# 03_LEDs_0_4.net
KiCad netlist of a schematic drawn in Altium Designer
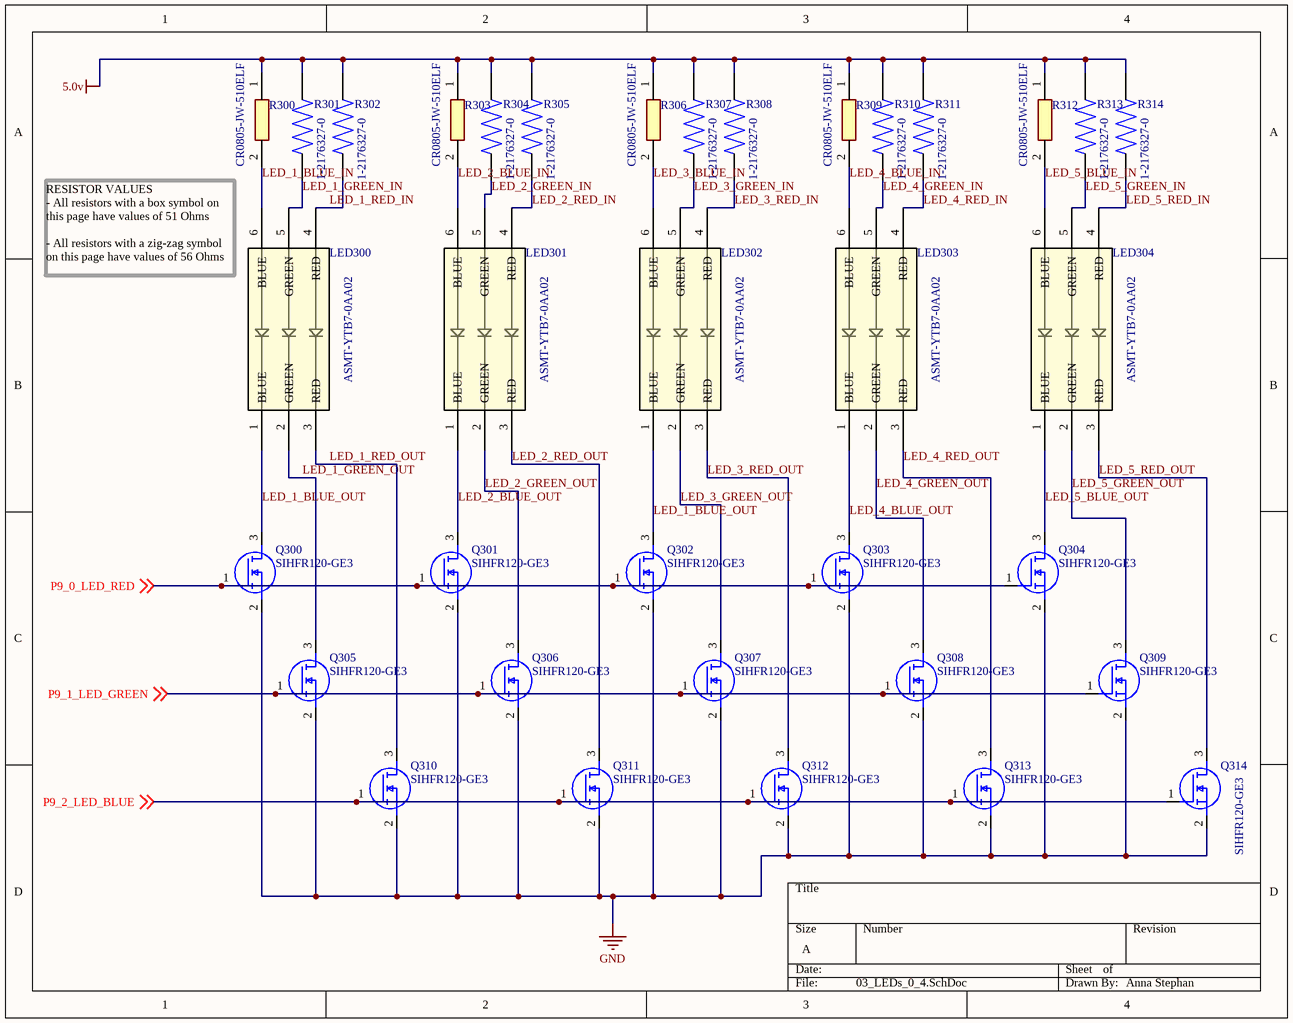
[diagram p0: 03_LEDs_0_4.SchDoc]

(export (version "E")
  (design (tool "Eeschema 10.0.6"))
  (components
    (comp (ref "LED300")
      (value "ASMT-YTB7-0AA02")
      (footprint "LED_ASMT-YTD7-0AA02")
      (description "No Description Available")
      (fields (field (name "COPYRIGHT") "Copyright (C) 2022 Ultra Librarian. All rights reserved."))
      (libsource (lib "453lib") (part "ASMT-YTB7-0AA02"))
    )
    (comp (ref "LED301")
      (value "ASMT-YTB7-0AA02")
      (footprint "LED_ASMT-YTD7-0AA02")
      (description "No Description Available")
      (fields (field (name "COPYRIGHT") "Copyright (C) 2022 Ultra Librarian. All rights reserved."))
      (libsource (lib "453lib") (part "ASMT-YTB7-0AA02"))
    )
    (comp (ref "LED302")
      (value "ASMT-YTB7-0AA02")
      (footprint "LED_ASMT-YTD7-0AA02")
      (description "No Description Available")
      (fields (field (name "COPYRIGHT") "Copyright (C) 2022 Ultra Librarian. All rights reserved."))
      (libsource (lib "453lib") (part "ASMT-YTB7-0AA02"))
    )
    (comp (ref "LED303")
      (value "ASMT-YTB7-0AA02")
      (footprint "LED_ASMT-YTD7-0AA02")
      (description "No Description Available")
      (fields (field (name "COPYRIGHT") "Copyright (C) 2022 Ultra Librarian. All rights reserved."))
      (libsource (lib "453lib") (part "ASMT-YTB7-0AA02"))
    )
    (comp (ref "LED304")
      (value "ASMT-YTB7-0AA02")
      (footprint "LED_ASMT-YTD7-0AA02")
      (description "No Description Available")
      (fields (field (name "COPYRIGHT") "Copyright (C) 2022 Ultra Librarian. All rights reserved."))
      (libsource (lib "453lib") (part "ASMT-YTB7-0AA02"))
    )
    (comp (ref "Q300")
      (value "SIHFR120-GE3")
      (footprint "SIHFR120GE3")
      (description "MOSFET (N-Channel)")
      (libsource (lib "453lib") (part "SIHFR120-GE3"))
    )
    (comp (ref "Q301")
      (value "SIHFR120-GE3")
      (footprint "SIHFR120GE3")
      (description "MOSFET (N-Channel)")
      (libsource (lib "453lib") (part "SIHFR120-GE3"))
    )
    (comp (ref "Q302")
      (value "SIHFR120-GE3")
      (footprint "SIHFR120GE3")
      (description "MOSFET (N-Channel)")
      (libsource (lib "453lib") (part "SIHFR120-GE3"))
    )
    (comp (ref "Q303")
      (value "SIHFR120-GE3")
      (footprint "SIHFR120GE3")
      (description "MOSFET (N-Channel)")
      (libsource (lib "453lib") (part "SIHFR120-GE3"))
    )
    (comp (ref "Q304")
      (value "SIHFR120-GE3")
      (footprint "SIHFR120GE3")
      (description "MOSFET (N-Channel)")
      (libsource (lib "453lib") (part "SIHFR120-GE3"))
    )
    (comp (ref "Q305")
      (value "SIHFR120-GE3")
      (footprint "SIHFR120GE3")
      (description "MOSFET (N-Channel)")
      (libsource (lib "453lib") (part "SIHFR120-GE3"))
    )
    (comp (ref "Q306")
      (value "SIHFR120-GE3")
      (footprint "SIHFR120GE3")
      (description "MOSFET (N-Channel)")
      (libsource (lib "453lib") (part "SIHFR120-GE3"))
    )
    (comp (ref "Q307")
      (value "SIHFR120-GE3")
      (footprint "SIHFR120GE3")
      (description "MOSFET (N-Channel)")
      (libsource (lib "453lib") (part "SIHFR120-GE3"))
    )
    (comp (ref "Q308")
      (value "SIHFR120-GE3")
      (footprint "SIHFR120GE3")
      (description "MOSFET (N-Channel)")
      (libsource (lib "453lib") (part "SIHFR120-GE3"))
    )
    (comp (ref "Q309")
      (value "SIHFR120-GE3")
      (footprint "SIHFR120GE3")
      (description "MOSFET (N-Channel)")
      (libsource (lib "453lib") (part "SIHFR120-GE3"))
    )
    (comp (ref "Q310")
      (value "SIHFR120-GE3")
      (footprint "SIHFR120GE3")
      (description "MOSFET (N-Channel)")
      (libsource (lib "453lib") (part "SIHFR120-GE3"))
    )
    (comp (ref "Q311")
      (value "SIHFR120-GE3")
      (footprint "SIHFR120GE3")
      (description "MOSFET (N-Channel)")
      (libsource (lib "453lib") (part "SIHFR120-GE3"))
    )
    (comp (ref "Q312")
      (value "SIHFR120-GE3")
      (footprint "SIHFR120GE3")
      (description "MOSFET (N-Channel)")
      (libsource (lib "453lib") (part "SIHFR120-GE3"))
    )
    (comp (ref "Q313")
      (value "SIHFR120-GE3")
      (footprint "SIHFR120GE3")
      (description "MOSFET (N-Channel)")
      (libsource (lib "453lib") (part "SIHFR120-GE3"))
    )
    (comp (ref "Q314")
      (value "SIHFR120-GE3")
      (footprint "SIHFR120GE3")
      (description "MOSFET (N-Channel)")
      (libsource (lib "453lib") (part "SIHFR120-GE3"))
    )
    (comp (ref "R300")
      (value "CR0805-JW-510ELF")
      (footprint "RESC2012X60N")
      (description "Resistor")
      (libsource (lib "453lib") (part "CR0805-JW-510ELF"))
    )
    (comp (ref "R301")
      (value "1-2176327-0")
      (footprint "RESC2012X65N")
      (description "Fixed Resistor CRGP 0805 56R 1%")
      (libsource (lib "453lib") (part "1-2176327-0"))
    )
    (comp (ref "R302")
      (value "1-2176327-0")
      (footprint "RESC2012X65N")
      (description "Fixed Resistor CRGP 0805 56R 1%")
      (libsource (lib "453lib") (part "1-2176327-0"))
    )
    (comp (ref "R303")
      (value "CR0805-JW-510ELF")
      (footprint "RESC2012X60N")
      (description "Resistor")
      (libsource (lib "453lib") (part "CR0805-JW-510ELF"))
    )
    (comp (ref "R304")
      (value "1-2176327-0")
      (footprint "RESC2012X65N")
      (description "Fixed Resistor CRGP 0805 56R 1%")
      (libsource (lib "453lib") (part "1-2176327-0"))
    )
    (comp (ref "R305")
      (value "1-2176327-0")
      (footprint "RESC2012X65N")
      (description "Fixed Resistor CRGP 0805 56R 1%")
      (libsource (lib "453lib") (part "1-2176327-0"))
    )
    (comp (ref "R306")
      (value "CR0805-JW-510ELF")
      (footprint "RESC2012X60N")
      (description "Resistor")
      (libsource (lib "453lib") (part "CR0805-JW-510ELF"))
    )
    (comp (ref "R307")
      (value "1-2176327-0")
      (footprint "RESC2012X65N")
      (description "Fixed Resistor CRGP 0805 56R 1%")
      (libsource (lib "453lib") (part "1-2176327-0"))
    )
    (comp (ref "R308")
      (value "1-2176327-0")
      (footprint "RESC2012X65N")
      (description "Fixed Resistor CRGP 0805 56R 1%")
      (libsource (lib "453lib") (part "1-2176327-0"))
    )
    (comp (ref "R309")
      (value "CR0805-JW-510ELF")
      (footprint "RESC2012X60N")
      (description "Resistor")
      (libsource (lib "453lib") (part "CR0805-JW-510ELF"))
    )
    (comp (ref "R310")
      (value "1-2176327-0")
      (footprint "RESC2012X65N")
      (description "Fixed Resistor CRGP 0805 56R 1%")
      (libsource (lib "453lib") (part "1-2176327-0"))
    )
    (comp (ref "R311")
      (value "1-2176327-0")
      (footprint "RESC2012X65N")
      (description "Fixed Resistor CRGP 0805 56R 1%")
      (libsource (lib "453lib") (part "1-2176327-0"))
    )
    (comp (ref "R312")
      (value "CR0805-JW-510ELF")
      (footprint "RESC2012X60N")
      (description "Resistor")
      (libsource (lib "453lib") (part "CR0805-JW-510ELF"))
    )
    (comp (ref "R313")
      (value "1-2176327-0")
      (footprint "RESC2012X65N")
      (description "Fixed Resistor CRGP 0805 56R 1%")
      (libsource (lib "453lib") (part "1-2176327-0"))
    )
    (comp (ref "R314")
      (value "1-2176327-0")
      (footprint "RESC2012X65N")
      (description "Fixed Resistor CRGP 0805 56R 1%")
      (libsource (lib "453lib") (part "1-2176327-0"))
    )
  )
  (nets
    (net (code "1") (name "/LED_1_BLUE_IN") (class "Default")
      (node (ref "LED300") (pin "6") (pinfunction "BLUE_6") (pintype "passive"))
      (node (ref "R300") (pin "2") (pinfunction "2_2") (pintype "passive"))
    )
    (net (code "2") (name "/LED_1_BLUE_OUT") (class "Default")
      (node (ref "LED300") (pin "1") (pinfunction "BLUE_1") (pintype "passive"))
      (node (ref "LED302") (pin "1") (pinfunction "BLUE_1") (pintype "passive"))
      (node (ref "Q300") (pin "3") (pinfunction "D_3") (pintype "passive"))
      (node (ref "Q302") (pin "3") (pinfunction "D_3") (pintype "passive"))
    )
    (net (code "3") (name "/LED_1_GREEN_IN") (class "Default")
      (node (ref "LED300") (pin "5") (pinfunction "GREEN_5") (pintype "passive"))
      (node (ref "R301") (pin "1") (pinfunction "1_1") (pintype "passive"))
    )
    (net (code "4") (name "/LED_1_GREEN_OUT") (class "Default")
      (node (ref "LED300") (pin "2") (pinfunction "GREEN_2") (pintype "passive"))
      (node (ref "Q305") (pin "3") (pinfunction "D_3") (pintype "passive"))
    )
    (net (code "5") (name "/LED_1_RED_IN") (class "Default")
      (node (ref "LED300") (pin "4") (pinfunction "RED_4") (pintype "passive"))
      (node (ref "R302") (pin "1") (pinfunction "1_1") (pintype "passive"))
    )
    (net (code "6") (name "/LED_1_RED_OUT") (class "Default")
      (node (ref "LED300") (pin "3") (pinfunction "RED_3") (pintype "passive"))
      (node (ref "Q310") (pin "3") (pinfunction "D_3") (pintype "passive"))
    )
    (net (code "7") (name "/LED_2_BLUE_IN") (class "Default")
      (node (ref "LED301") (pin "6") (pinfunction "BLUE_6") (pintype "passive"))
      (node (ref "R303") (pin "2") (pinfunction "2_2") (pintype "passive"))
    )
    (net (code "8") (name "/LED_2_BLUE_OUT") (class "Default")
      (node (ref "LED301") (pin "1") (pinfunction "BLUE_1") (pintype "passive"))
      (node (ref "Q301") (pin "3") (pinfunction "D_3") (pintype "passive"))
    )
    (net (code "9") (name "/LED_2_GREEN_IN") (class "Default")
      (node (ref "LED301") (pin "5") (pinfunction "GREEN_5") (pintype "passive"))
      (node (ref "R304") (pin "1") (pinfunction "1_1") (pintype "passive"))
    )
    (net (code "10") (name "/LED_2_GREEN_OUT") (class "Default")
      (node (ref "LED301") (pin "2") (pinfunction "GREEN_2") (pintype "passive"))
      (node (ref "Q306") (pin "3") (pinfunction "D_3") (pintype "passive"))
    )
    (net (code "11") (name "/LED_2_RED_IN") (class "Default")
      (node (ref "LED301") (pin "4") (pinfunction "RED_4") (pintype "passive"))
      (node (ref "R305") (pin "1") (pinfunction "1_1") (pintype "passive"))
    )
    (net (code "12") (name "/LED_2_RED_OUT") (class "Default")
      (node (ref "LED301") (pin "3") (pinfunction "RED_3") (pintype "passive"))
      (node (ref "Q311") (pin "3") (pinfunction "D_3") (pintype "passive"))
    )
    (net (code "13") (name "/LED_3_BLUE_IN") (class "Default")
      (node (ref "LED302") (pin "6") (pinfunction "BLUE_6") (pintype "passive"))
      (node (ref "R306") (pin "2") (pinfunction "2_2") (pintype "passive"))
    )
    (net (code "14") (name "/LED_3_GREEN_IN") (class "Default")
      (node (ref "LED302") (pin "5") (pinfunction "GREEN_5") (pintype "passive"))
      (node (ref "R307") (pin "1") (pinfunction "1_1") (pintype "passive"))
    )
    (net (code "15") (name "/LED_3_GREEN_OUT") (class "Default")
      (node (ref "LED302") (pin "2") (pinfunction "GREEN_2") (pintype "passive"))
      (node (ref "Q307") (pin "3") (pinfunction "D_3") (pintype "passive"))
    )
    (net (code "16") (name "/LED_3_RED_IN") (class "Default")
      (node (ref "LED302") (pin "4") (pinfunction "RED_4") (pintype "passive"))
      (node (ref "R308") (pin "1") (pinfunction "1_1") (pintype "passive"))
    )
    (net (code "17") (name "/LED_3_RED_OUT") (class "Default")
      (node (ref "LED302") (pin "3") (pinfunction "RED_3") (pintype "passive"))
      (node (ref "Q312") (pin "3") (pinfunction "D_3") (pintype "passive"))
    )
    (net (code "18") (name "/LED_4_BLUE_IN") (class "Default")
      (node (ref "LED303") (pin "6") (pinfunction "BLUE_6") (pintype "passive"))
      (node (ref "R309") (pin "2") (pinfunction "2_2") (pintype "passive"))
    )
    (net (code "19") (name "/LED_4_BLUE_OUT") (class "Default")
      (node (ref "LED303") (pin "1") (pinfunction "BLUE_1") (pintype "passive"))
      (node (ref "Q303") (pin "3") (pinfunction "D_3") (pintype "passive"))
    )
    (net (code "20") (name "/LED_4_GREEN_IN") (class "Default")
      (node (ref "LED303") (pin "5") (pinfunction "GREEN_5") (pintype "passive"))
      (node (ref "R310") (pin "1") (pinfunction "1_1") (pintype "passive"))
    )
    (net (code "21") (name "/LED_4_GREEN_OUT") (class "Default")
      (node (ref "LED303") (pin "2") (pinfunction "GREEN_2") (pintype "passive"))
      (node (ref "Q308") (pin "3") (pinfunction "D_3") (pintype "passive"))
    )
    (net (code "22") (name "/LED_4_RED_IN") (class "Default")
      (node (ref "LED303") (pin "4") (pinfunction "RED_4") (pintype "passive"))
      (node (ref "R311") (pin "1") (pinfunction "1_1") (pintype "passive"))
    )
    (net (code "23") (name "/LED_4_RED_OUT") (class "Default")
      (node (ref "LED303") (pin "3") (pinfunction "RED_3") (pintype "passive"))
      (node (ref "Q313") (pin "3") (pinfunction "D_3") (pintype "passive"))
    )
    (net (code "24") (name "/LED_5_BLUE_IN") (class "Default")
      (node (ref "LED304") (pin "6") (pinfunction "BLUE_6") (pintype "passive"))
      (node (ref "R312") (pin "2") (pinfunction "2_2") (pintype "passive"))
    )
    (net (code "25") (name "/LED_5_BLUE_OUT") (class "Default")
      (node (ref "LED304") (pin "1") (pinfunction "BLUE_1") (pintype "passive"))
      (node (ref "Q304") (pin "3") (pinfunction "D_3") (pintype "passive"))
    )
    (net (code "26") (name "/LED_5_GREEN_IN") (class "Default")
      (node (ref "LED304") (pin "5") (pinfunction "GREEN_5") (pintype "passive"))
      (node (ref "R313") (pin "1") (pinfunction "1_1") (pintype "passive"))
    )
    (net (code "27") (name "/LED_5_GREEN_OUT") (class "Default")
      (node (ref "LED304") (pin "2") (pinfunction "GREEN_2") (pintype "passive"))
      (node (ref "Q309") (pin "3") (pinfunction "D_3") (pintype "passive"))
    )
    (net (code "28") (name "/LED_5_RED_IN") (class "Default")
      (node (ref "LED304") (pin "4") (pinfunction "RED_4") (pintype "passive"))
      (node (ref "R314") (pin "1") (pinfunction "1_1") (pintype "passive"))
    )
    (net (code "29") (name "/LED_5_RED_OUT") (class "Default")
      (node (ref "LED304") (pin "3") (pinfunction "RED_3") (pintype "passive"))
      (node (ref "Q314") (pin "3") (pinfunction "D_3") (pintype "passive"))
    )
    (net (code "30") (name "5.0v") (class "Default")
      (node (ref "R300") (pin "1") (pinfunction "1_1") (pintype "passive"))
      (node (ref "R301") (pin "2") (pinfunction "2_2") (pintype "passive"))
      (node (ref "R302") (pin "2") (pinfunction "2_2") (pintype "passive"))
      (node (ref "R303") (pin "1") (pinfunction "1_1") (pintype "passive"))
      (node (ref "R304") (pin "2") (pinfunction "2_2") (pintype "passive"))
      (node (ref "R305") (pin "2") (pinfunction "2_2") (pintype "passive"))
      (node (ref "R306") (pin "1") (pinfunction "1_1") (pintype "passive"))
      (node (ref "R307") (pin "2") (pinfunction "2_2") (pintype "passive"))
      (node (ref "R308") (pin "2") (pinfunction "2_2") (pintype "passive"))
      (node (ref "R309") (pin "1") (pinfunction "1_1") (pintype "passive"))
      (node (ref "R310") (pin "2") (pinfunction "2_2") (pintype "passive"))
      (node (ref "R311") (pin "2") (pinfunction "2_2") (pintype "passive"))
      (node (ref "R312") (pin "1") (pinfunction "1_1") (pintype "passive"))
      (node (ref "R313") (pin "2") (pinfunction "2_2") (pintype "passive"))
      (node (ref "R314") (pin "2") (pinfunction "2_2") (pintype "passive"))
    )
    (net (code "31") (name "GND") (class "Default")
      (node (ref "Q300") (pin "2") (pinfunction "S_2") (pintype "passive"))
      (node (ref "Q301") (pin "2") (pinfunction "S_2") (pintype "passive"))
      (node (ref "Q302") (pin "2") (pinfunction "S_2") (pintype "passive"))
      (node (ref "Q303") (pin "2") (pinfunction "S_2") (pintype "passive"))
      (node (ref "Q304") (pin "2") (pinfunction "S_2") (pintype "passive"))
      (node (ref "Q305") (pin "2") (pinfunction "S_2") (pintype "passive"))
      (node (ref "Q306") (pin "2") (pinfunction "S_2") (pintype "passive"))
      (node (ref "Q307") (pin "2") (pinfunction "S_2") (pintype "passive"))
      (node (ref "Q308") (pin "2") (pinfunction "S_2") (pintype "passive"))
      (node (ref "Q309") (pin "2") (pinfunction "S_2") (pintype "passive"))
      (node (ref "Q310") (pin "2") (pinfunction "S_2") (pintype "passive"))
      (node (ref "Q311") (pin "2") (pinfunction "S_2") (pintype "passive"))
      (node (ref "Q312") (pin "2") (pinfunction "S_2") (pintype "passive"))
      (node (ref "Q313") (pin "2") (pinfunction "S_2") (pintype "passive"))
      (node (ref "Q314") (pin "2") (pinfunction "S_2") (pintype "passive"))
    )
    (net (code "32") (name "P9_0_LED_RED") (class "Default")
      (node (ref "Q300") (pin "1") (pinfunction "G_1") (pintype "passive"))
      (node (ref "Q301") (pin "1") (pinfunction "G_1") (pintype "passive"))
      (node (ref "Q302") (pin "1") (pinfunction "G_1") (pintype "passive"))
      (node (ref "Q303") (pin "1") (pinfunction "G_1") (pintype "passive"))
      (node (ref "Q304") (pin "1") (pinfunction "G_1") (pintype "passive"))
    )
    (net (code "33") (name "P9_1_LED_GREEN") (class "Default")
      (node (ref "Q305") (pin "1") (pinfunction "G_1") (pintype "passive"))
      (node (ref "Q306") (pin "1") (pinfunction "G_1") (pintype "passive"))
      (node (ref "Q307") (pin "1") (pinfunction "G_1") (pintype "passive"))
      (node (ref "Q308") (pin "1") (pinfunction "G_1") (pintype "passive"))
      (node (ref "Q309") (pin "1") (pinfunction "G_1") (pintype "passive"))
    )
    (net (code "34") (name "P9_2_LED_BLUE") (class "Default")
      (node (ref "Q310") (pin "1") (pinfunction "G_1") (pintype "passive"))
      (node (ref "Q311") (pin "1") (pinfunction "G_1") (pintype "passive"))
      (node (ref "Q312") (pin "1") (pinfunction "G_1") (pintype "passive"))
      (node (ref "Q313") (pin "1") (pinfunction "G_1") (pintype "passive"))
      (node (ref "Q314") (pin "1") (pinfunction "G_1") (pintype "passive"))
    )
  )
)
